# tm7_dock.net
KiCad netlist of a schematic drawn in EAGLE
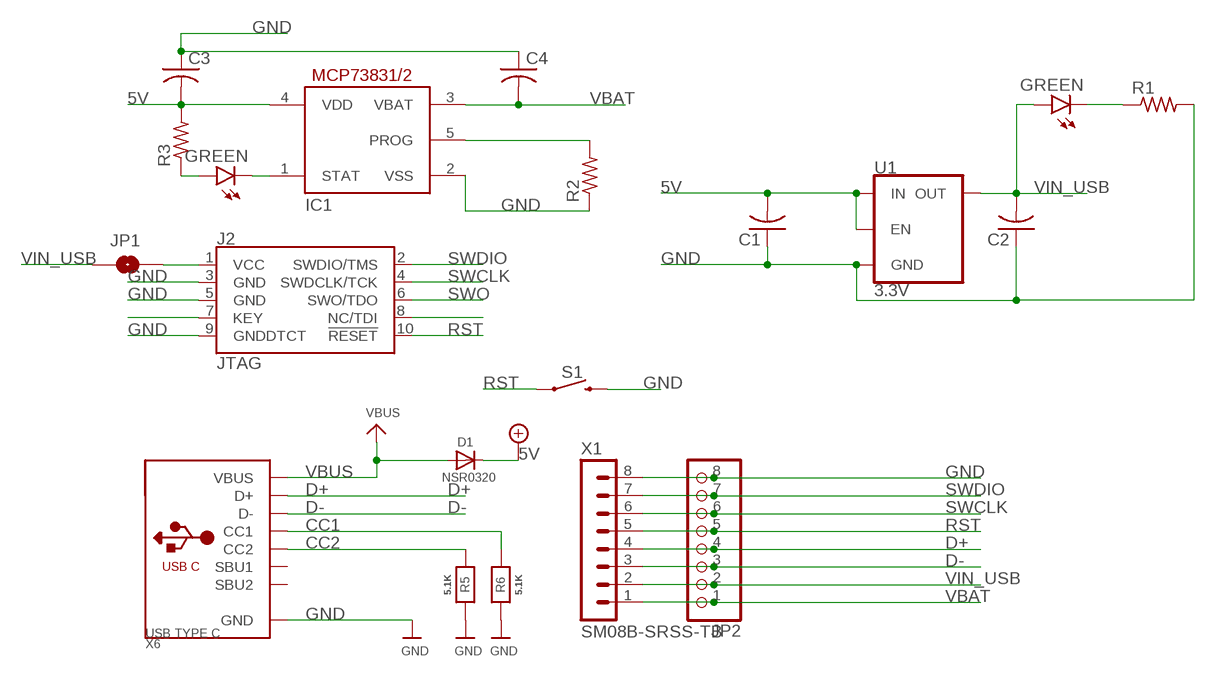
[diagram p0: schematic, sheet 1]

(export (version "E")
  (design (tool "Eeschema 10.0.6"))
  (components
    (comp (ref "C1")
      (value "C-USC0603")
      (footprint "eagle-import:C0603")
      (libsource (lib "eagle-import") (part "C-USC0603"))
    )
    (comp (ref "C2")
      (value "C-USC0603")
      (footprint "eagle-import:C0603")
      (libsource (lib "eagle-import") (part "C-USC0603"))
    )
    (comp (ref "C3")
      (value "C-USC0603")
      (footprint "eagle-import:C0603")
      (libsource (lib "eagle-import") (part "C-USC0603"))
    )
    (comp (ref "C4")
      (value "C-USC0603")
      (footprint "eagle-import:C0603")
      (libsource (lib "eagle-import") (part "C-USC0603"))
    )
    (comp (ref "D1")
      (value "NSR0320")
      (footprint "eagle-import:SOD-323_MINI")
      (libsource (lib "eagle-import") (part "DIODE_SOD323MINI"))
    )
    (comp (ref "D2")
      (value "GREEN")
      (footprint "eagle-import:LED-1206")
      (libsource (lib "eagle-import") (part "LED-GREEN1206"))
    )
    (comp (ref "D3")
      (value "GREEN")
      (footprint "eagle-import:LED-1206")
      (libsource (lib "eagle-import") (part "LED-GREEN1206"))
    )
    (comp (ref "IC1")
      (value "MCP73831/OT")
      (footprint "eagle-import:SOT23-5L")
      (libsource (lib "eagle-import") (part "MCP73831/OT"))
    )
    (comp (ref "J2")
      (value "JTAG")
      (footprint "eagle-import:2X5-SMD-1.27MM")
      (libsource (lib "eagle-import") (part "CORTEX_JTAG_DEBUG_SMD"))
    )
    (comp (ref "JP1")
      (value "JUMPER-SMT_2_NO_NO-SILK")
      (footprint "eagle-import:SMT-JUMPER_2_NO_NO-SILK")
      (libsource (lib "eagle-import") (part "JUMPER-SMT_2_NO_NO-SILK"))
    )
    (comp (ref "JP2")
      (value "PINHD-1X8LOCK")
      (footprint "eagle-import:1X08-LOCK")
      (libsource (lib "eagle-import") (part "PINHD-1X8LOCK"))
    )
    (comp (ref "R1")
      (value "R-US_R0603")
      (footprint "eagle-import:R0603")
      (libsource (lib "eagle-import") (part "R-US_R0603"))
    )
    (comp (ref "R2")
      (value "R-US_R0603")
      (footprint "eagle-import:R0603")
      (libsource (lib "eagle-import") (part "R-US_R0603"))
    )
    (comp (ref "R3")
      (value "R-US_R0603")
      (footprint "eagle-import:R0603")
      (libsource (lib "eagle-import") (part "R-US_R0603"))
    )
    (comp (ref "R5")
      (value "5.1K")
      (footprint "eagle-import:_0402NO")
      (libsource (lib "eagle-import") (part "RESISTOR_0402NO"))
    )
    (comp (ref "R6")
      (value "5.1K")
      (footprint "eagle-import:_0402NO")
      (libsource (lib "eagle-import") (part "RESISTOR_0402NO"))
    )
    (comp (ref "S1")
      (value "MOMENTARY-SWITCH-SPST-SMD-5.2MM-TALL")
      (footprint "eagle-import:TACTILE_SWITCH_SMD_5.2MM")
      (libsource (lib "eagle-import") (part "MOMENTARY-SWITCH-SPST-SMD-5.2MM-TALL"))
    )
    (comp (ref "U1")
      (value "3.3V")
      (footprint "eagle-import:SOT23-5")
      (libsource (lib "eagle-import") (part "V_REG_AP2112K-3.3V"))
    )
    (comp (ref "X1")
      (value "SM08B-SRSS-TB")
      (footprint "eagle-import:SM08B-SRSS-TB")
      (libsource (lib "eagle-import") (part "SM08B-SRSS-TB"))
    )
    (comp (ref "X6")
      (value "USB TYPE C")
      (footprint "eagle-import:USB_C_CUSB31-CFM2AX-01-X")
      (libsource (lib "eagle-import") (part "USB_C"))
    )
  )
  (nets
    (net (code "1") (name "+5V") (class "Default")
      (node (ref "C1") (pin "2") (pinfunction "2_2") (pintype "passive"))
      (node (ref "C3") (pin "2") (pinfunction "2_2") (pintype "passive"))
      (node (ref "D1") (pin "C") (pinfunction "C_C") (pintype "passive"))
      (node (ref "IC1") (pin "4") (pinfunction "VDD_4") (pintype "power_in"))
      (node (ref "R3") (pin "2") (pinfunction "2_2") (pintype "passive"))
      (node (ref "U1") (pin "1") (pinfunction "IN_1") (pintype "input"))
      (node (ref "U1") (pin "3") (pinfunction "EN_3") (pintype "input"))
    )
    (net (code "2") (name "/CC1") (class "Default")
      (node (ref "R6") (pin "2") (pinfunction "2_2") (pintype "passive"))
      (node (ref "X6") (pin "A5") (pinfunction "CC1_A5") (pintype "bidirectional"))
    )
    (net (code "3") (name "/CC2") (class "Default")
      (node (ref "R5") (pin "2") (pinfunction "2_2") (pintype "passive"))
      (node (ref "X6") (pin "B5") (pinfunction "CC2_B5") (pintype "bidirectional"))
    )
    (net (code "4") (name "/D+") (class "Default")
      (node (ref "JP2") (pin "4") (pinfunction "4_4") (pintype "passive"))
      (node (ref "X1") (pin "4") (pinfunction "4_4") (pintype "passive"))
      (node (ref "X6") (pin "A6") (pinfunction "D+_A6") (pintype "bidirectional"))
      (node (ref "X6") (pin "B6") (pinfunction "D+_B6") (pintype "bidirectional"))
    )
    (net (code "5") (name "/D-") (class "Default")
      (node (ref "JP2") (pin "3") (pinfunction "3_3") (pintype "passive"))
      (node (ref "X1") (pin "3") (pinfunction "3_3") (pintype "passive"))
      (node (ref "X6") (pin "A7") (pinfunction "D-_A7") (pintype "bidirectional"))
      (node (ref "X6") (pin "B7") (pinfunction "D-_B7") (pintype "bidirectional"))
    )
    (net (code "6") (name "/RST") (class "Default")
      (node (ref "J2") (pin "10") (pinfunction "~{RESET}_10") (pintype "bidirectional"))
      (node (ref "JP2") (pin "5") (pinfunction "5_5") (pintype "passive"))
      (node (ref "S1") (pin "1") (pinfunction "1_1") (pintype "passive"))
      (node (ref "X1") (pin "5") (pinfunction "5_5") (pintype "passive"))
    )
    (net (code "7") (name "/SWCLK") (class "Default")
      (node (ref "J2") (pin "4") (pinfunction "SWDCLK/TCK_4") (pintype "bidirectional"))
      (node (ref "JP2") (pin "6") (pinfunction "6_6") (pintype "passive"))
      (node (ref "X1") (pin "6") (pinfunction "6_6") (pintype "passive"))
    )
    (net (code "8") (name "/SWDIO") (class "Default")
      (node (ref "J2") (pin "2") (pinfunction "SWDIO/TMS_2") (pintype "bidirectional"))
      (node (ref "JP2") (pin "7") (pinfunction "7_7") (pintype "passive"))
      (node (ref "X1") (pin "7") (pinfunction "7_7") (pintype "passive"))
    )
    (net (code "9") (name "/SWO") (class "Default")
      (node (ref "J2") (pin "6") (pinfunction "SWO/TDO_6") (pintype "bidirectional"))
    )
    (net (code "10") (name "/VBAT") (class "Default")
      (node (ref "C4") (pin "2") (pinfunction "2_2") (pintype "passive"))
      (node (ref "IC1") (pin "3") (pinfunction "VBAT_3") (pintype "bidirectional"))
      (node (ref "JP2") (pin "1") (pinfunction "1_1") (pintype "passive"))
      (node (ref "X1") (pin "1") (pinfunction "1_1") (pintype "passive"))
    )
    (net (code "11") (name "/VIN_USB") (class "Default")
      (node (ref "C2") (pin "2") (pinfunction "2_2") (pintype "passive"))
      (node (ref "D2") (pin "A") (pinfunction "A_A") (pintype "passive"))
      (node (ref "JP1") (pin "1") (pinfunction "1_1") (pintype "passive"))
      (node (ref "JP2") (pin "2") (pinfunction "2_2") (pintype "passive"))
      (node (ref "U1") (pin "5") (pinfunction "OUT_5") (pintype "passive"))
      (node (ref "X1") (pin "2") (pinfunction "2_2") (pintype "passive"))
    )
    (net (code "12") (name "GND") (class "Default")
      (node (ref "C1") (pin "1") (pinfunction "1_1") (pintype "passive"))
      (node (ref "C2") (pin "1") (pinfunction "1_1") (pintype "passive"))
      (node (ref "C3") (pin "1") (pinfunction "1_1") (pintype "passive"))
      (node (ref "C4") (pin "1") (pinfunction "1_1") (pintype "passive"))
      (node (ref "IC1") (pin "2") (pinfunction "VSS_2") (pintype "power_in"))
      (node (ref "J2") (pin "3") (pinfunction "GND_3") (pintype "bidirectional"))
      (node (ref "J2") (pin "5") (pinfunction "GND_5") (pintype "bidirectional"))
      (node (ref "J2") (pin "9") (pinfunction "GNDDTCT_9") (pintype "bidirectional"))
      (node (ref "JP2") (pin "8") (pinfunction "8_8") (pintype "passive"))
      (node (ref "R1") (pin "2") (pinfunction "2_2") (pintype "passive"))
      (node (ref "R2") (pin "1") (pinfunction "1_1") (pintype "passive"))
      (node (ref "R5") (pin "1") (pinfunction "1_1") (pintype "passive"))
      (node (ref "R6") (pin "1") (pinfunction "1_1") (pintype "passive"))
      (node (ref "S1") (pin "3") (pinfunction "2_3") (pintype "passive"))
      (node (ref "U1") (pin "2") (pinfunction "GND_2") (pintype "input"))
      (node (ref "X1") (pin "8") (pinfunction "8_8") (pintype "passive"))
      (node (ref "X6") (pin "A1B12") (pinfunction "GND_A1B12") (pintype "power_in"))
      (node (ref "X6") (pin "B1A12") (pinfunction "GND_B1A12") (pintype "power_in"))
    )
    (net (code "13") (name "Net-(D2-PadC)") (class "Default")
      (node (ref "D2") (pin "C") (pinfunction "C_C") (pintype "passive"))
      (node (ref "R1") (pin "1") (pinfunction "1_1") (pintype "passive"))
    )
    (net (code "14") (name "Net-(D3-PadA)") (class "Default")
      (node (ref "D3") (pin "A") (pinfunction "A_A") (pintype "passive"))
      (node (ref "R3") (pin "1") (pinfunction "1_1") (pintype "passive"))
    )
    (net (code "15") (name "Net-(IC1-PROG)") (class "Default")
      (node (ref "IC1") (pin "5") (pinfunction "PROG_5") (pintype "input"))
      (node (ref "R2") (pin "2") (pinfunction "2_2") (pintype "passive"))
    )
    (net (code "16") (name "Net-(IC1-STAT)") (class "Default")
      (node (ref "D3") (pin "C") (pinfunction "C_C") (pintype "passive"))
      (node (ref "IC1") (pin "1") (pinfunction "STAT_1") (pintype "output"))
    )
    (net (code "17") (name "Net-(J2-VCC)") (class "Default")
      (node (ref "J2") (pin "1") (pinfunction "VCC_1") (pintype "bidirectional"))
      (node (ref "JP1") (pin "2") (pinfunction "2_2") (pintype "passive"))
    )
    (net (code "18") (name "VBUS") (class "Default")
      (node (ref "D1") (pin "A") (pinfunction "A_A") (pintype "passive"))
      (node (ref "X6") (pin "A4B9") (pinfunction "VBUS_A4B9") (pintype "power_in"))
      (node (ref "X6") (pin "B4A9") (pinfunction "VBUS_B4A9") (pintype "power_in"))
    )
    (net (code "19") (name "unconnected-(J2-KEY-Pad7)") (class "Default")
      (node (ref "J2") (pin "7") (pinfunction "KEY_7") (pintype "bidirectional"))
    )
    (net (code "20") (name "unconnected-(J2-NC{slash}TDI-Pad8)") (class "Default")
      (node (ref "J2") (pin "8") (pinfunction "NC/TDI_8") (pintype "bidirectional"))
    )
    (net (code "21") (name "unconnected-(X6-SBU1-PadA8)") (class "Default")
      (node (ref "X6") (pin "A8") (pinfunction "SBU1_A8") (pintype "bidirectional"))
    )
    (net (code "22") (name "unconnected-(X6-SBU2-PadB8)") (class "Default")
      (node (ref "X6") (pin "B8") (pinfunction "SBU2_B8") (pintype "bidirectional"))
    )
  )
)
